# CLOCK_TRIGGER_BUF_SMA.net
KiCad netlist of a schematic drawn in Altium Designer
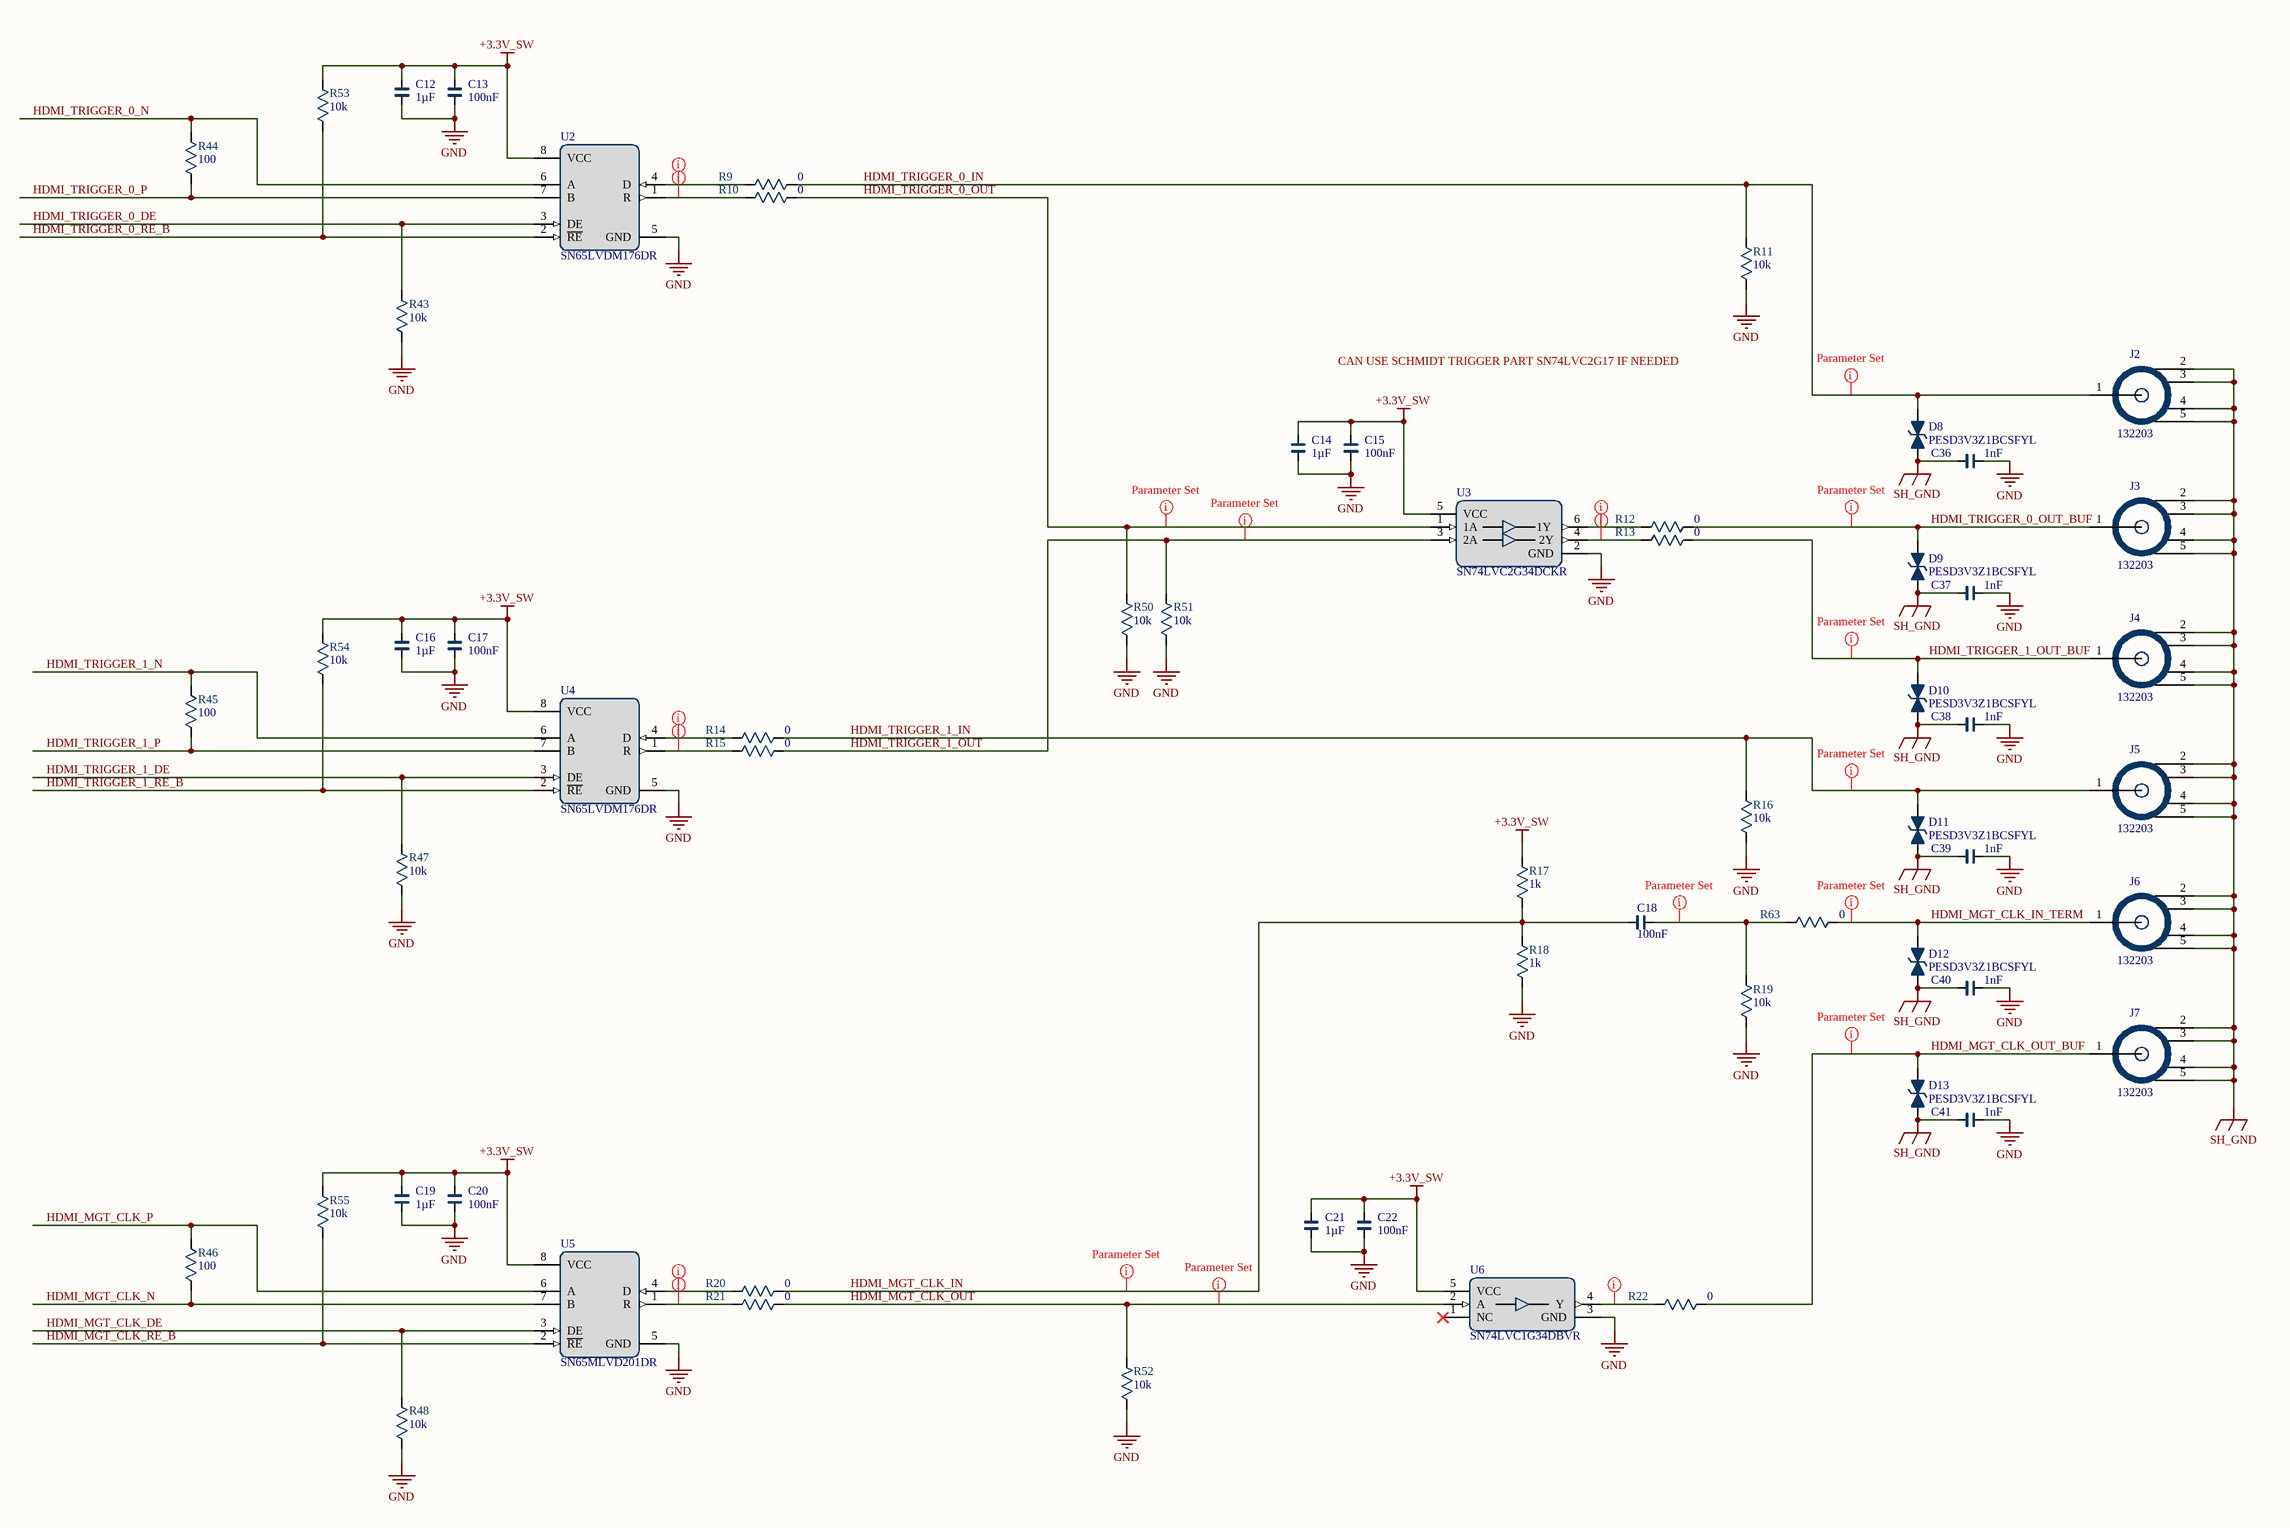
[diagram p0: CLOCK_TRIGGER_BUF_SMA.SchDoc]

(export (version "E")
  (design (tool "Eeschema 10.0.6"))
  (components
    (comp (ref "C12")
      (value "1µF")
      (footprint "CAPC160X80X95L35")
      (description "CAP CER 1uF 10V 10% 0603")
      (fields (field (name "VOLTAGE") "10V") (field (name "TOLERANCE") "10%"))
      (libsource (lib "") (part "CAP_1"))
    )
    (comp (ref "C13")
      (value "100nF")
      (footprint "CAPC160X80X95L35")
      (description "CAP CER 0.1UF 25V X7R 0603")
      (fields (field (name "VOLTAGE") "25V") (field (name "TOLERANCE") "10%"))
      (libsource (lib "") (part "CAP_1"))
    )
    (comp (ref "C14")
      (value "1µF")
      (footprint "CAPC160X80X95L35")
      (description "CAP CER 1uF 10V 10% 0603")
      (fields (field (name "VOLTAGE") "10V") (field (name "TOLERANCE") "10%"))
      (libsource (lib "") (part "CAP_1"))
    )
    (comp (ref "C15")
      (value "100nF")
      (footprint "CAPC160X80X95L35")
      (description "CAP CER 0.1UF 25V X7R 0603")
      (fields (field (name "VOLTAGE") "25V") (field (name "TOLERANCE") "10%"))
      (libsource (lib "") (part "CAP_1"))
    )
    (comp (ref "C16")
      (value "1µF")
      (footprint "CAPC160X80X95L35")
      (description "CAP CER 1uF 10V 10% 0603")
      (fields (field (name "VOLTAGE") "10V") (field (name "TOLERANCE") "10%"))
      (libsource (lib "") (part "CAP_1"))
    )
    (comp (ref "C17")
      (value "100nF")
      (footprint "CAPC160X80X95L35")
      (description "CAP CER 0.1UF 25V X7R 0603")
      (fields (field (name "VOLTAGE") "25V") (field (name "TOLERANCE") "10%"))
      (libsource (lib "") (part "CAP_1"))
    )
    (comp (ref "C18")
      (value "100nF")
      (footprint "CAPC160X80X95L35")
      (description "CAP CER 0.1UF 25V X7R 0603")
      (fields (field (name "VOLTAGE") "25V") (field (name "TOLERANCE") "10%"))
      (libsource (lib "") (part "CAP_2"))
    )
    (comp (ref "C19")
      (value "1µF")
      (footprint "CAPC160X80X95L35")
      (description "CAP CER 1uF 10V 10% 0603")
      (fields (field (name "VOLTAGE") "10V") (field (name "TOLERANCE") "10%"))
      (libsource (lib "") (part "CAP_1"))
    )
    (comp (ref "C20")
      (value "100nF")
      (footprint "CAPC160X80X95L35")
      (description "CAP CER 0.1UF 25V X7R 0603")
      (fields (field (name "VOLTAGE") "25V") (field (name "TOLERANCE") "10%"))
      (libsource (lib "") (part "CAP_1"))
    )
    (comp (ref "C21")
      (value "1µF")
      (footprint "CAPC160X80X95L35")
      (description "CAP CER 1uF 10V 10% 0603")
      (fields (field (name "VOLTAGE") "10V") (field (name "TOLERANCE") "10%"))
      (libsource (lib "") (part "CAP_1"))
    )
    (comp (ref "C22")
      (value "100nF")
      (footprint "CAPC160X80X95L35")
      (description "CAP CER 0.1UF 25V X7R 0603")
      (fields (field (name "VOLTAGE") "25V") (field (name "TOLERANCE") "10%"))
      (libsource (lib "") (part "CAP_1"))
    )
    (comp (ref "C36")
      (value "1nF")
      (footprint "CAPC160X80X95L35")
      (description "CAP CER 1000PF 50V C0G/NPO 0603")
      (fields (field (name "TOLERANCE") "5%") (field (name "VOLTAGE") "50V"))
      (libsource (lib "Atom Computing") (part "CAP"))
    )
    (comp (ref "C37")
      (value "1nF")
      (footprint "CAPC160X80X95L35")
      (description "CAP CER 1000PF 50V C0G/NPO 0603")
      (fields (field (name "TOLERANCE") "5%") (field (name "VOLTAGE") "50V"))
      (libsource (lib "Atom Computing") (part "CAP"))
    )
    (comp (ref "C38")
      (value "1nF")
      (footprint "CAPC160X80X95L35")
      (description "CAP CER 1000PF 50V C0G/NPO 0603")
      (fields (field (name "TOLERANCE") "5%") (field (name "VOLTAGE") "50V"))
      (libsource (lib "Atom Computing") (part "CAP"))
    )
    (comp (ref "C39")
      (value "1nF")
      (footprint "CAPC160X80X95L35")
      (description "CAP CER 1000PF 50V C0G/NPO 0603")
      (fields (field (name "TOLERANCE") "5%") (field (name "VOLTAGE") "50V"))
      (libsource (lib "Atom Computing") (part "CAP"))
    )
    (comp (ref "C40")
      (value "1nF")
      (footprint "CAPC160X80X95L35")
      (description "CAP CER 1000PF 50V C0G/NPO 0603")
      (fields (field (name "TOLERANCE") "5%") (field (name "VOLTAGE") "50V"))
      (libsource (lib "Atom Computing") (part "CAP"))
    )
    (comp (ref "C41")
      (value "1nF")
      (footprint "CAPC160X80X95L35")
      (description "CAP CER 1000PF 50V C0G/NPO 0603")
      (fields (field (name "TOLERANCE") "5%") (field (name "VOLTAGE") "50V"))
      (libsource (lib "Atom Computing") (part "CAP"))
    )
    (comp (ref "D8")
      (value "PESD3V3Z1BCSFYL")
      (footprint "DIO_PESD5V0R1BSFYL")
      (description "TVS DIODE 3.3VWM 4.8VC DSN0603-2")
      (fields (field (name "MFG") "Nexperia USA Inc."))
      (libsource (lib "Atom Computing") (part "DIODE_TVS_BI"))
    )
    (comp (ref "D9")
      (value "PESD3V3Z1BCSFYL")
      (footprint "DIO_PESD5V0R1BSFYL")
      (description "TVS DIODE 3.3VWM 4.8VC DSN0603-2")
      (fields (field (name "MFG") "Nexperia USA Inc."))
      (libsource (lib "Atom Computing") (part "DIODE_TVS_BI"))
    )
    (comp (ref "D10")
      (value "PESD3V3Z1BCSFYL")
      (footprint "DIO_PESD5V0R1BSFYL")
      (description "TVS DIODE 3.3VWM 4.8VC DSN0603-2")
      (fields (field (name "MFG") "Nexperia USA Inc."))
      (libsource (lib "Atom Computing") (part "DIODE_TVS_BI"))
    )
    (comp (ref "D11")
      (value "PESD3V3Z1BCSFYL")
      (footprint "DIO_PESD5V0R1BSFYL")
      (description "TVS DIODE 3.3VWM 4.8VC DSN0603-2")
      (fields (field (name "MFG") "Nexperia USA Inc."))
      (libsource (lib "Atom Computing") (part "DIODE_TVS_BI"))
    )
    (comp (ref "D12")
      (value "PESD3V3Z1BCSFYL")
      (footprint "DIO_PESD5V0R1BSFYL")
      (description "TVS DIODE 3.3VWM 4.8VC DSN0603-2")
      (fields (field (name "MFG") "Nexperia USA Inc."))
      (libsource (lib "Atom Computing") (part "DIODE_TVS_BI"))
    )
    (comp (ref "D13")
      (value "PESD3V3Z1BCSFYL")
      (footprint "DIO_PESD5V0R1BSFYL")
      (description "TVS DIODE 3.3VWM 4.8VC DSN0603-2")
      (fields (field (name "MFG") "Nexperia USA Inc."))
      (libsource (lib "Atom Computing") (part "DIODE_TVS_BI"))
    )
    (comp (ref "J2")
      (value "132203")
      (footprint "Amphenol_132203")
      (description "Conn; RF; SMA Rt Angle PCB Jack Thru Hole 50 Ohm Bulkhead")
      (fields (field (name "MFG") "Amphenol RF"))
      (libsource (lib "Atom Computing") (part "CONN_SMA"))
    )
    (comp (ref "J3")
      (value "132203")
      (footprint "Amphenol_132203")
      (description "Conn; RF; SMA Rt Angle PCB Jack Thru Hole 50 Ohm Bulkhead")
      (fields (field (name "MFG") "Amphenol RF"))
      (libsource (lib "Atom Computing") (part "CONN_SMA"))
    )
    (comp (ref "J4")
      (value "132203")
      (footprint "Amphenol_132203")
      (description "Conn; RF; SMA Rt Angle PCB Jack Thru Hole 50 Ohm Bulkhead")
      (fields (field (name "MFG") "Amphenol RF"))
      (libsource (lib "Atom Computing") (part "CONN_SMA"))
    )
    (comp (ref "J5")
      (value "132203")
      (footprint "Amphenol_132203")
      (description "Conn; RF; SMA Rt Angle PCB Jack Thru Hole 50 Ohm Bulkhead")
      (fields (field (name "MFG") "Amphenol RF"))
      (libsource (lib "Atom Computing") (part "CONN_SMA"))
    )
    (comp (ref "J6")
      (value "132203")
      (footprint "Amphenol_132203")
      (description "Conn; RF; SMA Rt Angle PCB Jack Thru Hole 50 Ohm Bulkhead")
      (fields (field (name "MFG") "Amphenol RF"))
      (libsource (lib "Atom Computing") (part "CONN_SMA"))
    )
    (comp (ref "J7")
      (value "132203")
      (footprint "Amphenol_132203")
      (description "Conn; RF; SMA Rt Angle PCB Jack Thru Hole 50 Ohm Bulkhead")
      (fields (field (name "MFG") "Amphenol RF"))
      (libsource (lib "Atom Computing") (part "CONN_SMA"))
    )
    (comp (ref "R9")
      (value "0")
      (footprint "RESC160X85X55L30")
      (description "RES 0 OHM JUMPER 1/10W 0603")
      (fields (field (name "MFG") "Yageo"))
      (libsource (lib "Atom Computing") (part "RES"))
    )
    (comp (ref "R10")
      (value "0")
      (footprint "RESC160X85X55L30")
      (description "RES 0 OHM JUMPER 1/10W 0603")
      (fields (field (name "MFG") "Yageo"))
      (libsource (lib "Atom Computing") (part "RES"))
    )
    (comp (ref "R11")
      (value "10k")
      (footprint "RESC160X85X55L30")
      (description "RES SMD 10K OHM 1% 1/10W 0603")
      (fields (field (name "POWER") "100mW") (field (name "MFG") "Panasonic Electronic Components"))
      (libsource (lib "Atom Computing") (part "RES"))
    )
    (comp (ref "R12")
      (value "0")
      (footprint "RESC160X85X55L30")
      (description "RES 0 OHM JUMPER 1/10W 0603")
      (fields (field (name "MFG") "Yageo"))
      (libsource (lib "Atom Computing") (part "RES"))
    )
    (comp (ref "R13")
      (value "0")
      (footprint "RESC160X85X55L30")
      (description "RES 0 OHM JUMPER 1/10W 0603")
      (fields (field (name "MFG") "Yageo"))
      (libsource (lib "Atom Computing") (part "RES"))
    )
    (comp (ref "R14")
      (value "0")
      (footprint "RESC160X85X55L30")
      (description "RES 0 OHM JUMPER 1/10W 0603")
      (fields (field (name "MFG") "Yageo"))
      (libsource (lib "Atom Computing") (part "RES"))
    )
    (comp (ref "R15")
      (value "0")
      (footprint "RESC160X85X55L30")
      (description "RES 0 OHM JUMPER 1/10W 0603")
      (fields (field (name "MFG") "Yageo"))
      (libsource (lib "Atom Computing") (part "RES"))
    )
    (comp (ref "R16")
      (value "10k")
      (footprint "RESC160X85X55L30")
      (description "RES SMD 10K OHM 1% 1/10W 0603")
      (fields (field (name "POWER") "100mW") (field (name "MFG") "Panasonic Electronic Components"))
      (libsource (lib "Atom Computing") (part "RES"))
    )
    (comp (ref "R17")
      (value "1k")
      (footprint "RESC160X85X55L30")
      (description "RES SMD 1K OHM 1% 1/10W 0603")
      (fields (field (name "MFG") "Yageo"))
      (libsource (lib "Atom Computing") (part "RES"))
    )
    (comp (ref "R18")
      (value "1k")
      (footprint "RESC160X85X55L30")
      (description "RES SMD 1K OHM 1% 1/10W 0603")
      (fields (field (name "MFG") "Yageo"))
      (libsource (lib "Atom Computing") (part "RES"))
    )
    (comp (ref "R19")
      (value "10k")
      (footprint "RESC160X85X55L30")
      (description "RES SMD 10K OHM 1% 1/10W 0603")
      (fields (field (name "POWER") "100mW") (field (name "MFG") "Panasonic Electronic Components"))
      (libsource (lib "Atom Computing") (part "RES"))
    )
    (comp (ref "R20")
      (value "0")
      (footprint "RESC160X85X55L30")
      (description "RES 0 OHM JUMPER 1/10W 0603")
      (fields (field (name "MFG") "Yageo"))
      (libsource (lib "Atom Computing") (part "RES"))
    )
    (comp (ref "R21")
      (value "0")
      (footprint "RESC160X85X55L30")
      (description "RES 0 OHM JUMPER 1/10W 0603")
      (fields (field (name "MFG") "Yageo"))
      (libsource (lib "Atom Computing") (part "RES"))
    )
    (comp (ref "R22")
      (value "0")
      (footprint "RESC160X85X55L30")
      (description "RES 0 OHM JUMPER 1/10W 0603")
      (fields (field (name "MFG") "Yageo"))
      (libsource (lib "Atom Computing") (part "RES"))
    )
    (comp (ref "R43")
      (value "10k")
      (footprint "RESC160X85X55L30")
      (description "RES SMD 10K OHM 1% 1/10W 0603")
      (fields (field (name "POWER") "100mW") (field (name "MFG") "Panasonic Electronic Components"))
      (libsource (lib "Atom Computing") (part "RES"))
    )
    (comp (ref "R44")
      (value "100")
      (footprint "RESC160X85X55L30")
      (description "RES SMD 100 OHM 1% 1/10W 0603")
      (fields (field (name "POWER") "100mW") (field (name "TOLERANCE") "1%"))
      (libsource (lib "Atom Computing") (part "RES"))
    )
    (comp (ref "R45")
      (value "100")
      (footprint "RESC160X85X55L30")
      (description "RES SMD 100 OHM 1% 1/10W 0603")
      (fields (field (name "POWER") "100mW") (field (name "TOLERANCE") "1%"))
      (libsource (lib "Atom Computing") (part "RES"))
    )
    (comp (ref "R46")
      (value "100")
      (footprint "RESC160X85X55L30")
      (description "RES SMD 100 OHM 1% 1/10W 0603")
      (fields (field (name "POWER") "100mW") (field (name "TOLERANCE") "1%"))
      (libsource (lib "Atom Computing") (part "RES"))
    )
    (comp (ref "R47")
      (value "10k")
      (footprint "RESC160X85X55L30")
      (description "RES SMD 10K OHM 1% 1/10W 0603")
      (fields (field (name "POWER") "100mW") (field (name "MFG") "Panasonic Electronic Components"))
      (libsource (lib "Atom Computing") (part "RES"))
    )
    (comp (ref "R48")
      (value "10k")
      (footprint "RESC160X85X55L30")
      (description "RES SMD 10K OHM 1% 1/10W 0603")
      (fields (field (name "POWER") "100mW") (field (name "MFG") "Panasonic Electronic Components"))
      (libsource (lib "Atom Computing") (part "RES"))
    )
    (comp (ref "R50")
      (value "10k")
      (footprint "RESC160X85X55L30")
      (description "RES SMD 10K OHM 1% 1/10W 0603")
      (fields (field (name "POWER") "100mW") (field (name "MFG") "Panasonic Electronic Components"))
      (libsource (lib "Atom Computing") (part "RES"))
    )
    (comp (ref "R51")
      (value "10k")
      (footprint "RESC160X85X55L30")
      (description "RES SMD 10K OHM 1% 1/10W 0603")
      (fields (field (name "POWER") "100mW") (field (name "MFG") "Panasonic Electronic Components"))
      (libsource (lib "Atom Computing") (part "RES"))
    )
    (comp (ref "R52")
      (value "10k")
      (footprint "RESC160X85X55L30")
      (description "RES SMD 10K OHM 1% 1/10W 0603")
      (fields (field (name "POWER") "100mW") (field (name "MFG") "Panasonic Electronic Components"))
      (libsource (lib "Atom Computing") (part "RES"))
    )
    (comp (ref "R53")
      (value "10k")
      (footprint "RESC160X85X55L30")
      (description "RES SMD 10K OHM 1% 1/10W 0603")
      (fields (field (name "POWER") "100mW") (field (name "MFG") "Panasonic Electronic Components"))
      (libsource (lib "Atom Computing") (part "RES"))
    )
    (comp (ref "R54")
      (value "10k")
      (footprint "RESC160X85X55L30")
      (description "RES SMD 10K OHM 1% 1/10W 0603")
      (fields (field (name "POWER") "100mW") (field (name "MFG") "Panasonic Electronic Components"))
      (libsource (lib "Atom Computing") (part "RES"))
    )
    (comp (ref "R55")
      (value "10k")
      (footprint "RESC160X85X55L30")
      (description "RES SMD 10K OHM 1% 1/10W 0603")
      (fields (field (name "POWER") "100mW") (field (name "MFG") "Panasonic Electronic Components"))
      (libsource (lib "Atom Computing") (part "RES"))
    )
    (comp (ref "R63")
      (value "0")
      (footprint "RESC160X85X55L30")
      (description "RES 0 OHM JUMPER 1/10W 0603")
      (fields (field (name "MFG") "Yageo"))
      (libsource (lib "Atom Computing") (part "RES"))
    )
    (comp (ref "U2")
      (value "SN65LVDM176DR")
      (footprint "SOIC8P127_490X599X175L84X41")
      (description "1/1 Transceiver Half LVDS 8-SOIC")
      (fields (field (name "MFG") "Texas Instruments"))
      (libsource (lib "Atom Computing") (part "SN65LVDM176DR"))
    )
    (comp (ref "U3")
      (value "SN74LVC2G34DCKR")
      (footprint "SOT23-6P65_210X110L36X23")
      (description "Buffer, Non-Inverting 2 Element 1 Bit per Element Push-Pull Output SC-70-6")
      (fields (field (name "MFG") "Texas Instruments"))
      (libsource (lib "Atom Computing") (part "SN74LVC2G34"))
    )
    (comp (ref "U4")
      (value "SN65LVDM176DR")
      (footprint "SOIC8P127_490X599X175L84X41")
      (description "1/1 Transceiver Half LVDS 8-SOIC")
      (fields (field (name "MFG") "Texas Instruments"))
      (libsource (lib "Atom Computing") (part "SN65LVDM176DR"))
    )
    (comp (ref "U5")
      (value "SN65MLVD201DR")
      (footprint "SOIC8P127_490X599X175L84X41")
      (description "1/1 Transceiver Half LVDS, Multipoint 8-SOIC")
      (fields (field (name "MFG") "Texas Instruments"))
      (libsource (lib "Atom Computing") (part "SN65MLVD201DR"))
    )
    (comp (ref "U6")
      (value "SN74LVC1G34DBVR")
      (footprint "SOT23-5P95_280X110L45X40")
      (description "Buffer, Non-Inverting 1 Element 1 Bit per Element Push-Pull Output SOT-23-5")
      (fields (field (name "MFG") "Texas Instruments"))
      (libsource (lib "Atom Computing") (part "SN74LVC1G34DVB"))
    )
  )
  (nets
    (net (code "1") (name "+3.3V_SW") (class "Default")
      (node (ref "C12") (pin "1") (pinfunction "1_1") (pintype "passive"))
      (node (ref "C13") (pin "1") (pinfunction "1_1") (pintype "passive"))
      (node (ref "C14") (pin "1") (pinfunction "1_1") (pintype "passive"))
      (node (ref "C15") (pin "1") (pinfunction "1_1") (pintype "passive"))
      (node (ref "C16") (pin "1") (pinfunction "1_1") (pintype "passive"))
      (node (ref "C17") (pin "1") (pinfunction "1_1") (pintype "passive"))
      (node (ref "C19") (pin "1") (pinfunction "1_1") (pintype "passive"))
      (node (ref "C20") (pin "1") (pinfunction "1_1") (pintype "passive"))
      (node (ref "C21") (pin "1") (pinfunction "1_1") (pintype "passive"))
      (node (ref "C22") (pin "1") (pinfunction "1_1") (pintype "passive"))
      (node (ref "R17") (pin "2") (pinfunction "2_2") (pintype "passive"))
      (node (ref "R53") (pin "2") (pinfunction "2_2") (pintype "passive"))
      (node (ref "R54") (pin "2") (pinfunction "2_2") (pintype "passive"))
      (node (ref "R55") (pin "2") (pinfunction "2_2") (pintype "passive"))
      (node (ref "U2") (pin "8") (pinfunction "VCC_8") (pintype "power_in"))
      (node (ref "U3") (pin "5") (pinfunction "VCC_5") (pintype "power_in"))
      (node (ref "U4") (pin "8") (pinfunction "VCC_8") (pintype "power_in"))
      (node (ref "U5") (pin "8") (pinfunction "VCC_8") (pintype "power_in"))
      (node (ref "U6") (pin "5") (pinfunction "VCC_5") (pintype "power_in"))
    )
    (net (code "2") (name "/HDMI_MGT_CLK_DE") (class "Default")
      (node (ref "R48") (pin "2") (pinfunction "2_2") (pintype "passive"))
      (node (ref "U5") (pin "3") (pinfunction "DE_3") (pintype "input"))
    )
    (net (code "3") (name "/HDMI_MGT_CLK_IN") (class "Default")
      (node (ref "C18") (pin "1") (pinfunction "1_1") (pintype "passive"))
      (node (ref "R17") (pin "1") (pinfunction "1_1") (pintype "passive"))
      (node (ref "R18") (pin "2") (pinfunction "2_2") (pintype "passive"))
      (node (ref "R20") (pin "2") (pinfunction "2_2") (pintype "passive"))
    )
    (net (code "4") (name "/HDMI_MGT_CLK_IN_TERM") (class "Default")
      (node (ref "D12") (pin "2") (pinfunction "2_2") (pintype "passive"))
      (node (ref "J6") (pin "1") (pinfunction "RF_1") (pintype "passive"))
      (node (ref "R63") (pin "2") (pinfunction "2_2") (pintype "passive"))
    )
    (net (code "5") (name "/HDMI_MGT_CLK_N") (class "Default")
      (node (ref "R46") (pin "1") (pinfunction "1_1") (pintype "passive"))
      (node (ref "U5") (pin "7") (pinfunction "B_7") (pintype "passive"))
    )
    (net (code "6") (name "/HDMI_MGT_CLK_OUT") (class "Default")
      (node (ref "R21") (pin "2") (pinfunction "2_2") (pintype "passive"))
      (node (ref "R52") (pin "2") (pinfunction "2_2") (pintype "passive"))
      (node (ref "U6") (pin "2") (pinfunction "A_2") (pintype "input"))
    )
    (net (code "7") (name "/HDMI_MGT_CLK_OUT_BUF") (class "Default")
      (node (ref "D13") (pin "2") (pinfunction "2_2") (pintype "passive"))
      (node (ref "J7") (pin "1") (pinfunction "RF_1") (pintype "passive"))
      (node (ref "R22") (pin "2") (pinfunction "2_2") (pintype "passive"))
    )
    (net (code "8") (name "/HDMI_MGT_CLK_P") (class "Default")
      (node (ref "R46") (pin "2") (pinfunction "2_2") (pintype "passive"))
      (node (ref "U5") (pin "6") (pinfunction "A_6") (pintype "passive"))
    )
    (net (code "9") (name "/HDMI_MGT_CLK_RE_B") (class "Default")
      (node (ref "R55") (pin "1") (pinfunction "1_1") (pintype "passive"))
      (node (ref "U5") (pin "2") (pinfunction "~{RE}_2") (pintype "input"))
    )
    (net (code "10") (name "/HDMI_TRIGGER_0_DE") (class "Default")
      (node (ref "R43") (pin "2") (pinfunction "2_2") (pintype "passive"))
      (node (ref "U2") (pin "3") (pinfunction "DE_3") (pintype "input"))
    )
    (net (code "11") (name "/HDMI_TRIGGER_0_IN") (class "Default")
      (node (ref "D8") (pin "2") (pinfunction "2_2") (pintype "passive"))
      (node (ref "J2") (pin "1") (pinfunction "RF_1") (pintype "passive"))
      (node (ref "R11") (pin "2") (pinfunction "2_2") (pintype "passive"))
      (node (ref "R9") (pin "2") (pinfunction "2_2") (pintype "passive"))
    )
    (net (code "12") (name "/HDMI_TRIGGER_0_N") (class "Default")
      (node (ref "R44") (pin "2") (pinfunction "2_2") (pintype "passive"))
      (node (ref "U2") (pin "6") (pinfunction "A_6") (pintype "passive"))
    )
    (net (code "13") (name "/HDMI_TRIGGER_0_OUT") (class "Default")
      (node (ref "R10") (pin "2") (pinfunction "2_2") (pintype "passive"))
      (node (ref "R50") (pin "2") (pinfunction "2_2") (pintype "passive"))
      (node (ref "U3") (pin "1") (pinfunction "1A_1") (pintype "input"))
    )
    (net (code "14") (name "/HDMI_TRIGGER_0_OUT_BUF") (class "Default")
      (node (ref "D9") (pin "2") (pinfunction "2_2") (pintype "passive"))
      (node (ref "J3") (pin "1") (pinfunction "RF_1") (pintype "passive"))
      (node (ref "R12") (pin "2") (pinfunction "2_2") (pintype "passive"))
    )
    (net (code "15") (name "/HDMI_TRIGGER_0_P") (class "Default")
      (node (ref "R44") (pin "1") (pinfunction "1_1") (pintype "passive"))
      (node (ref "U2") (pin "7") (pinfunction "B_7") (pintype "passive"))
    )
    (net (code "16") (name "/HDMI_TRIGGER_0_RE_B") (class "Default")
      (node (ref "R53") (pin "1") (pinfunction "1_1") (pintype "passive"))
      (node (ref "U2") (pin "2") (pinfunction "~{RE}_2") (pintype "input"))
    )
    (net (code "17") (name "/HDMI_TRIGGER_1_DE") (class "Default")
      (node (ref "R47") (pin "2") (pinfunction "2_2") (pintype "passive"))
      (node (ref "U4") (pin "3") (pinfunction "DE_3") (pintype "input"))
    )
    (net (code "18") (name "/HDMI_TRIGGER_1_IN") (class "Default")
      (node (ref "D11") (pin "2") (pinfunction "2_2") (pintype "passive"))
      (node (ref "J5") (pin "1") (pinfunction "RF_1") (pintype "passive"))
      (node (ref "R14") (pin "2") (pinfunction "2_2") (pintype "passive"))
      (node (ref "R16") (pin "2") (pinfunction "2_2") (pintype "passive"))
    )
    (net (code "19") (name "/HDMI_TRIGGER_1_N") (class "Default")
      (node (ref "R45") (pin "2") (pinfunction "2_2") (pintype "passive"))
      (node (ref "U4") (pin "6") (pinfunction "A_6") (pintype "passive"))
    )
    (net (code "20") (name "/HDMI_TRIGGER_1_OUT") (class "Default")
      (node (ref "R15") (pin "2") (pinfunction "2_2") (pintype "passive"))
      (node (ref "R51") (pin "2") (pinfunction "2_2") (pintype "passive"))
      (node (ref "U3") (pin "3") (pinfunction "2A_3") (pintype "input"))
    )
    (net (code "21") (name "/HDMI_TRIGGER_1_OUT_BUF") (class "Default")
      (node (ref "D10") (pin "2") (pinfunction "2_2") (pintype "passive"))
      (node (ref "J4") (pin "1") (pinfunction "RF_1") (pintype "passive"))
      (node (ref "R13") (pin "2") (pinfunction "2_2") (pintype "passive"))
    )
    (net (code "22") (name "/HDMI_TRIGGER_1_P") (class "Default")
      (node (ref "R45") (pin "1") (pinfunction "1_1") (pintype "passive"))
      (node (ref "U4") (pin "7") (pinfunction "B_7") (pintype "passive"))
    )
    (net (code "23") (name "/HDMI_TRIGGER_1_RE_B") (class "Default")
      (node (ref "R54") (pin "1") (pinfunction "1_1") (pintype "passive"))
      (node (ref "U4") (pin "2") (pinfunction "~{RE}_2") (pintype "input"))
    )
    (net (code "24") (name "GND") (class "Default")
      (node (ref "C12") (pin "2") (pinfunction "2_2") (pintype "passive"))
      (node (ref "C13") (pin "2") (pinfunction "2_2") (pintype "passive"))
      (node (ref "C14") (pin "2") (pinfunction "2_2") (pintype "passive"))
      (node (ref "C15") (pin "2") (pinfunction "2_2") (pintype "passive"))
      (node (ref "C16") (pin "2") (pinfunction "2_2") (pintype "passive"))
      (node (ref "C17") (pin "2") (pinfunction "2_2") (pintype "passive"))
      (node (ref "C19") (pin "2") (pinfunction "2_2") (pintype "passive"))
      (node (ref "C20") (pin "2") (pinfunction "2_2") (pintype "passive"))
      (node (ref "C21") (pin "2") (pinfunction "2_2") (pintype "passive"))
      (node (ref "C22") (pin "2") (pinfunction "2_2") (pintype "passive"))
      (node (ref "C36") (pin "1") (pinfunction "1_1") (pintype "passive"))
      (node (ref "C37") (pin "1") (pinfunction "1_1") (pintype "passive"))
      (node (ref "C38") (pin "1") (pinfunction "1_1") (pintype "passive"))
      (node (ref "C39") (pin "1") (pinfunction "1_1") (pintype "passive"))
      (node (ref "C40") (pin "1") (pinfunction "1_1") (pintype "passive"))
      (node (ref "C41") (pin "1") (pinfunction "1_1") (pintype "passive"))
      (node (ref "R11") (pin "1") (pinfunction "1_1") (pintype "passive"))
      (node (ref "R16") (pin "1") (pinfunction "1_1") (pintype "passive"))
      (node (ref "R18") (pin "1") (pinfunction "1_1") (pintype "passive"))
      (node (ref "R19") (pin "1") (pinfunction "1_1") (pintype "passive"))
      (node (ref "R43") (pin "1") (pinfunction "1_1") (pintype "passive"))
      (node (ref "R47") (pin "1") (pinfunction "1_1") (pintype "passive"))
      (node (ref "R48") (pin "1") (pinfunction "1_1") (pintype "passive"))
      (node (ref "R50") (pin "1") (pinfunction "1_1") (pintype "passive"))
      (node (ref "R51") (pin "1") (pinfunction "1_1") (pintype "passive"))
      (node (ref "R52") (pin "1") (pinfunction "1_1") (pintype "passive"))
      (node (ref "U2") (pin "5") (pinfunction "GND_5") (pintype "power_in"))
      (node (ref "U3") (pin "2") (pinfunction "GND_2") (pintype "power_in"))
      (node (ref "U4") (pin "5") (pinfunction "GND_5") (pintype "power_in"))
      (node (ref "U5") (pin "5") (pinfunction "GND_5") (pintype "power_in"))
      (node (ref "U6") (pin "3") (pinfunction "GND_3") (pintype "power_in"))
    )
    (net (code "25") (name "Net-(C18-Pad2)") (class "Default")
      (node (ref "C18") (pin "2") (pinfunction "2_2") (pintype "passive"))
      (node (ref "R19") (pin "2") (pinfunction "2_2") (pintype "passive"))
      (node (ref "R63") (pin "1") (pinfunction "1_1") (pintype "passive"))
    )
    (net (code "26") (name "Net-(U2-D)") (class "Default")
      (node (ref "R9") (pin "1") (pinfunction "1_1") (pintype "passive"))
      (node (ref "U2") (pin "4") (pinfunction "D_4") (pintype "input"))
    )
    (net (code "27") (name "Net-(U2-R)") (class "Default")
      (node (ref "R10") (pin "1") (pinfunction "1_1") (pintype "passive"))
      (node (ref "U2") (pin "1") (pinfunction "R_1") (pintype "output"))
    )
    (net (code "28") (name "Net-(U3-1Y)") (class "Default")
      (node (ref "R12") (pin "1") (pinfunction "1_1") (pintype "passive"))
      (node (ref "U3") (pin "6") (pinfunction "1Y_6") (pintype "output"))
    )
    (net (code "29") (name "Net-(U3-2Y)") (class "Default")
      (node (ref "R13") (pin "1") (pinfunction "1_1") (pintype "passive"))
      (node (ref "U3") (pin "4") (pinfunction "2Y_4") (pintype "output"))
    )
    (net (code "30") (name "Net-(U4-D)") (class "Default")
      (node (ref "R14") (pin "1") (pinfunction "1_1") (pintype "passive"))
      (node (ref "U4") (pin "4") (pinfunction "D_4") (pintype "input"))
    )
    (net (code "31") (name "Net-(U4-R)") (class "Default")
      (node (ref "R15") (pin "1") (pinfunction "1_1") (pintype "passive"))
      (node (ref "U4") (pin "1") (pinfunction "R_1") (pintype "output"))
    )
    (net (code "32") (name "Net-(U5-D)") (class "Default")
      (node (ref "R20") (pin "1") (pinfunction "1_1") (pintype "passive"))
      (node (ref "U5") (pin "4") (pinfunction "D_4") (pintype "input"))
    )
    (net (code "33") (name "Net-(U5-R)") (class "Default")
      (node (ref "R21") (pin "1") (pinfunction "1_1") (pintype "passive"))
      (node (ref "U5") (pin "1") (pinfunction "R_1") (pintype "output"))
    )
    (net (code "34") (name "Net-(U6-Y)") (class "Default")
      (node (ref "R22") (pin "1") (pinfunction "1_1") (pintype "passive"))
      (node (ref "U6") (pin "4") (pinfunction "Y_4") (pintype "output"))
    )
    (net (code "35") (name "SH_GND") (class "Default")
      (node (ref "C36") (pin "2") (pinfunction "2_2") (pintype "passive"))
      (node (ref "C37") (pin "2") (pinfunction "2_2") (pintype "passive"))
      (node (ref "C38") (pin "2") (pinfunction "2_2") (pintype "passive"))
      (node (ref "C39") (pin "2") (pinfunction "2_2") (pintype "passive"))
      (node (ref "C40") (pin "2") (pinfunction "2_2") (pintype "passive"))
      (node (ref "C41") (pin "2") (pinfunction "2_2") (pintype "passive"))
      (node (ref "D10") (pin "1") (pinfunction "1_1") (pintype "passive"))
      (node (ref "D11") (pin "1") (pinfunction "1_1") (pintype "passive"))
      (node (ref "D12") (pin "1") (pinfunction "1_1") (pintype "passive"))
      (node (ref "D13") (pin "1") (pinfunction "1_1") (pintype "passive"))
      (node (ref "D8") (pin "1") (pinfunction "1_1") (pintype "passive"))
      (node (ref "D9") (pin "1") (pinfunction "1_1") (pintype "passive"))
      (node (ref "J2") (pin "2") (pinfunction "GND_2") (pintype "passive"))
      (node (ref "J2") (pin "3") (pinfunction "GND_3") (pintype "passive"))
      (node (ref "J2") (pin "4") (pinfunction "GND_4") (pintype "passive"))
      (node (ref "J2") (pin "5") (pinfunction "GND_5") (pintype "passive"))
      (node (ref "J3") (pin "2") (pinfunction "GND_2") (pintype "passive"))
      (node (ref "J3") (pin "3") (pinfunction "GND_3") (pintype "passive"))
      (node (ref "J3") (pin "4") (pinfunction "GND_4") (pintype "passive"))
      (node (ref "J3") (pin "5") (pinfunction "GND_5") (pintype "passive"))
      (node (ref "J4") (pin "2") (pinfunction "GND_2") (pintype "passive"))
      (node (ref "J4") (pin "3") (pinfunction "GND_3") (pintype "passive"))
      (node (ref "J4") (pin "4") (pinfunction "GND_4") (pintype "passive"))
      (node (ref "J4") (pin "5") (pinfunction "GND_5") (pintype "passive"))
      (node (ref "J5") (pin "2") (pinfunction "GND_2") (pintype "passive"))
      (node (ref "J5") (pin "3") (pinfunction "GND_3") (pintype "passive"))
      (node (ref "J5") (pin "4") (pinfunction "GND_4") (pintype "passive"))
      (node (ref "J5") (pin "5") (pinfunction "GND_5") (pintype "passive"))
      (node (ref "J6") (pin "2") (pinfunction "GND_2") (pintype "passive"))
      (node (ref "J6") (pin "3") (pinfunction "GND_3") (pintype "passive"))
      (node (ref "J6") (pin "4") (pinfunction "GND_4") (pintype "passive"))
      (node (ref "J6") (pin "5") (pinfunction "GND_5") (pintype "passive"))
      (node (ref "J7") (pin "2") (pinfunction "GND_2") (pintype "passive"))
      (node (ref "J7") (pin "3") (pinfunction "GND_3") (pintype "passive"))
      (node (ref "J7") (pin "4") (pinfunction "GND_4") (pintype "passive"))
      (node (ref "J7") (pin "5") (pinfunction "GND_5") (pintype "passive"))
    )
    (net (code "36") (name "unconnected-(U6-NC-Pad1)") (class "Default")
      (node (ref "U6") (pin "1") (pinfunction "NC_1") (pintype "passive+no_connect"))
    )
  )
)
